# CH32V005F6U.net
KiCad netlist of a schematic drawn in Altium Designer
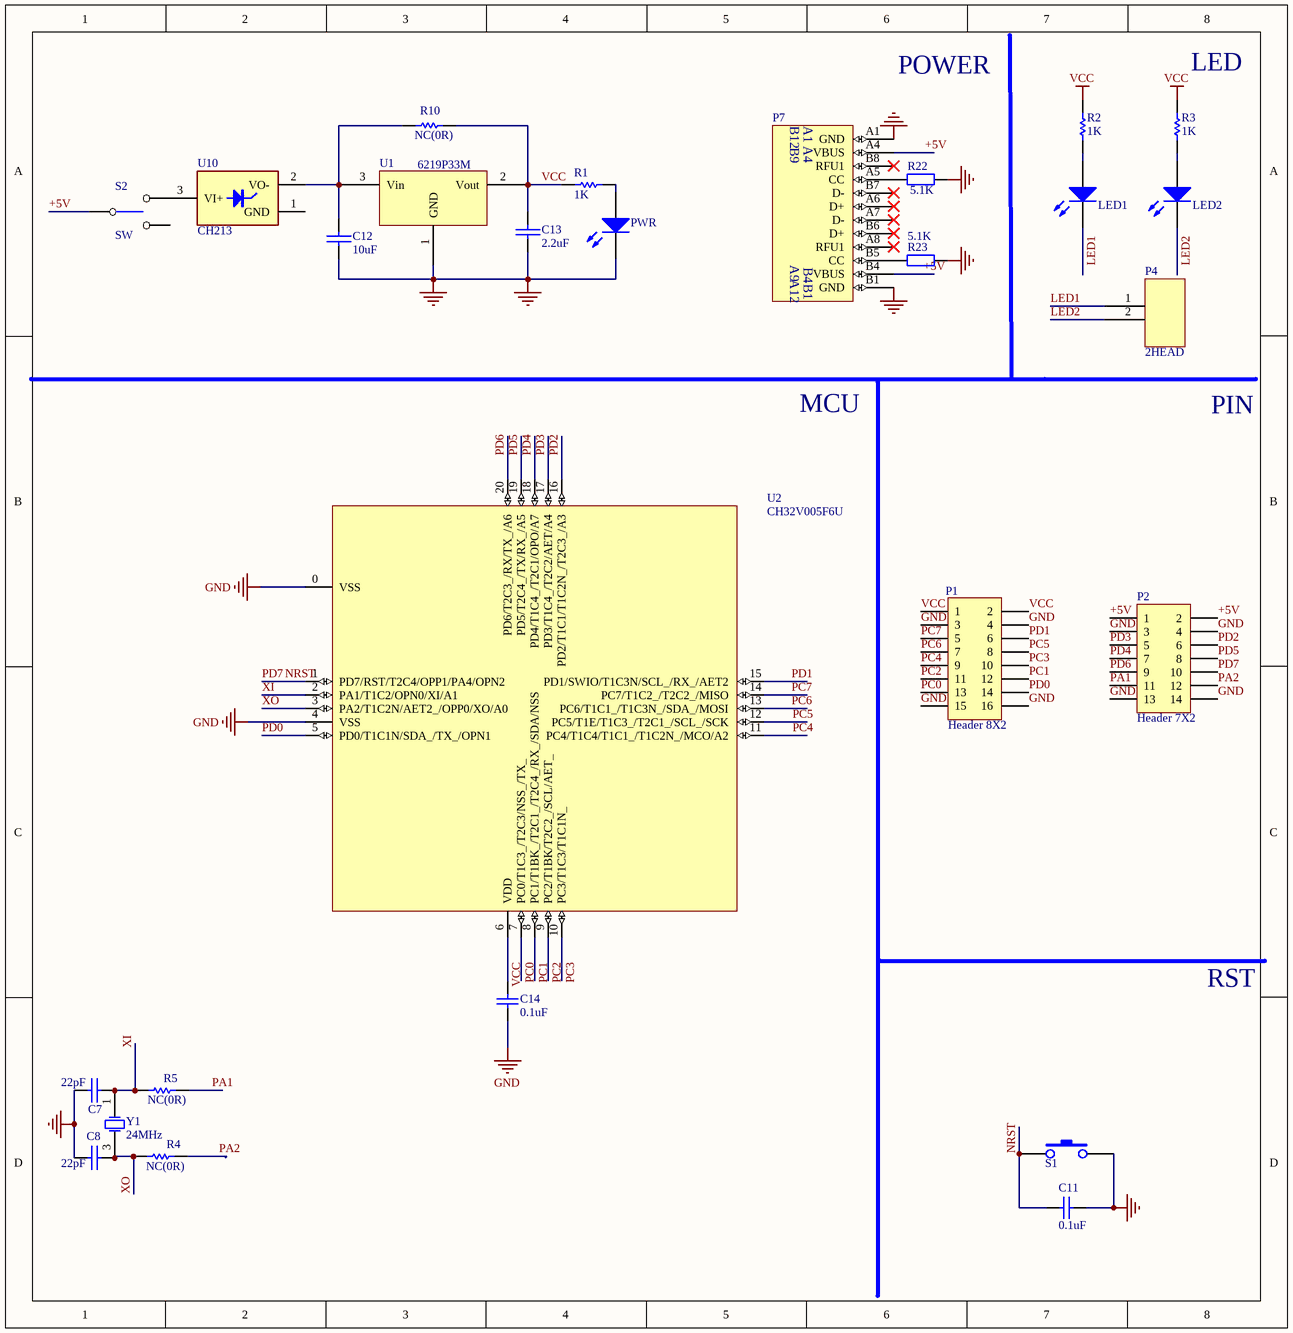
[diagram p0: CH32V005F6U.SchDoc]

(export (version "E")
  (design (tool "Eeschema 10.0.6"))
  (components
    (comp (ref "C7")
      (value "22pF")
      (footprint "0402_C")
      (description "Capacitor")
      (libsource (lib "*") (part "CAP"))
    )
    (comp (ref "C8")
      (value "22pF")
      (footprint "0402_C")
      (description "Capacitor")
      (libsource (lib "*") (part "CAP"))
    )
    (comp (ref "C11")
      (value "0.1uF")
      (footprint "0603_C")
      (description "Capacitor")
      (fields (field (name "PUBLISHER") "Altium Limited"))
      (libsource (lib "*") (part "Cap"))
    )
    (comp (ref "C12")
      (value "10uF")
      (footprint "0603_C")
      (description "Capacitor")
      (libsource (lib "wch_sch_others") (part "CAP"))
    )
    (comp (ref "C13")
      (value "2.2uF")
      (footprint "0402_C")
      (description "Capacitor")
      (libsource (lib "wch_sch_others") (part "CAP"))
    )
    (comp (ref "C14")
      (value "0.1uF")
      (footprint "0603_C")
      (description "Capacitor")
      (fields (field (name "PUBLISHER") "Altium Limited"))
      (libsource (lib "*") (part "Cap"))
    )
    (comp (ref "LED1")
      (value "LED1   blue")
      (footprint "0603+")
      (description "Typical INFRARED GaAs LED")
      (fields (field (name "PUBLISHER") "Altium Limited"))
      (libsource (lib "*") (part "LED0"))
    )
    (comp (ref "LED2")
      (value "LED2  blue")
      (footprint "0603+")
      (description "Typical INFRARED GaAs LED")
      (fields (field (name "PUBLISHER") "Altium Limited"))
      (libsource (lib "*") (part "LED0"))
    )
    (comp (ref "P1")
      (value "Header 8X2")
      (footprint "HDR2X8")
      (description "Header, 8-Pin, Dual row")
      (fields (field (name "PUBLISHER") "Altium Limited"))
      (libsource (lib "Miscellaneous Connectors") (part "Header 8X2"))
    )
    (comp (ref "P2")
      (value "Header 7X2")
      (footprint "HDR2X7")
      (description "Header, 7-Pin, Dual row")
      (fields (field (name "PUBLISHER") "Altium Limited"))
      (libsource (lib "Miscellaneous Connectors") (part "Header 7X2"))
    )
    (comp (ref "P4") (value "2HEAD") (footprint "SIP2-2.54mm") (libsource (lib "*") (part "2HEAD")))
    (comp (ref "P7")
      (value "TYPE-C")
      (footprint "TYPE-C-Receptacle-2.0")
      (libsource (lib "*") (part "TYPE-C1"))
    )
    (comp (ref "PWR")
      (value "POWER  red")
      (footprint "0603+")
      (description "Typical INFRARED GaAs LED")
      (fields (field (name "PUBLISHER") "Altium Limited"))
      (libsource (lib "") (part "LED0_1"))
    )
    (comp (ref "R1")
      (value "1K")
      (footprint "0402")
      (description "Semiconductor Resistor")
      (fields (field (name "PUBLISHER") "Altium Limited"))
      (libsource (lib "*") (part "Res Semi"))
    )
    (comp (ref "R2")
      (value "1K")
      (footprint "0402")
      (description "Semiconductor Resistor")
      (fields (field (name "PUBLISHER") "Altium Limited"))
      (libsource (lib "*") (part "Res Semi"))
    )
    (comp (ref "R3")
      (value "1K")
      (footprint "0402")
      (description "Semiconductor Resistor")
      (fields (field (name "PUBLISHER") "Altium Limited"))
      (libsource (lib "*") (part "Res Semi"))
    )
    (comp (ref "R4")
      (value "NC(0R)")
      (footprint "0402")
      (description "Semiconductor Resistor")
      (fields (field (name "Comment") "0R") (field (name "PUBLISHER") "Altium Limited"))
      (libsource (lib "*") (part "Res Semi"))
    )
    (comp (ref "R5")
      (value "NC(0R)")
      (footprint "0402")
      (description "Semiconductor Resistor")
      (fields (field (name "Comment") "0R") (field (name "PUBLISHER") "Altium Limited"))
      (libsource (lib "*") (part "Res Semi"))
    )
    (comp (ref "R10")
      (value "NC(0R)")
      (footprint "0402")
      (description "Semiconductor Resistor")
      (fields (field (name "Comment") "0R") (field (name "PUBLISHER") "Altium Limited"))
      (libsource (lib "*") (part "Res Semi"))
    )
    (comp (ref "R22")
      (value "5.1K")
      (footprint "0402")
      (description "Resistor")
      (libsource (lib "Miscellaneous Devices") (part "Res2"))
    )
    (comp (ref "R23")
      (value "5.1K")
      (footprint "0402")
      (description "Resistor")
      (libsource (lib "Miscellaneous Devices") (part "Res2"))
    )
    (comp (ref "S1") (value "NRST") (footprint "SMD_6.1x3.65x2.5mm-KEY") (libsource (lib "*") (part "KEY")))
    (comp (ref "S2") (value "SW") (footprint "SW1") (libsource (lib "*") (part "SW")))
    (comp (ref "U1")
      (value "6219P33M")
      (footprint "SOT-23")
      (libsource (lib "wch_sch_others") (part "6219P33M"))
    )
    (comp (ref "U2")
      (value "CH32V005F6U")
      (footprint "QFN20_3X3")
      (description "RISC-V MCU, 48MHz, ADC/OPA/2*UART/I2C/SPI")
      (libsource (lib "DHXXXSCH") (part "CH32V005F6U6"))
    )
    (comp (ref "U10")
      (value "CH213")
      (footprint "SOT-23-3")
      (description "Ideal Diode 5V*1A")
      (libsource (lib "CHXXX") (part "CH213E"))
    )
    (comp (ref "Y1")
      (value "24MHz")
      (footprint "XT3225")
      (description "Crystal Oscillator")
      (fields (field (name "PUBLISHER") "Altium Limited"))
      (libsource (lib "*") (part "XTAL"))
    )
  )
  (nets
    (net (code "1") (name "/+5V") (class "Default")
      (node (ref "P2") (pin "1") (pinfunction "1_1") (pintype "passive"))
      (node (ref "P2") (pin "2") (pinfunction "2_2") (pintype "passive"))
      (node (ref "P7") (pin "A4") (pinfunction "VBUS_A4") (pintype "bidirectional"))
      (node (ref "P7") (pin "B4") (pinfunction "VBUS_B4") (pintype "bidirectional"))
      (node (ref "S2") (pin "1") (pinfunction "1_1") (pintype "passive"))
    )
    (net (code "2") (name "/LED1") (class "Default")
      (node (ref "LED1") (pin "2") (pinfunction "K_2") (pintype "passive"))
      (node (ref "P4") (pin "1") (pintype "passive"))
    )
    (net (code "3") (name "/LED2") (class "Default")
      (node (ref "LED2") (pin "2") (pinfunction "K_2") (pintype "passive"))
      (node (ref "P4") (pin "2") (pintype "passive"))
    )
    (net (code "4") (name "/NRST") (class "Default")
      (node (ref "C11") (pin "2") (pinfunction "2_2") (pintype "passive"))
      (node (ref "P2") (pin "10") (pinfunction "10_10") (pintype "passive"))
      (node (ref "S1") (pin "1") (pinfunction "1_1") (pintype "passive"))
      (node (ref "U2") (pin "1") (pinfunction "PD7/RST/T2C4/OPP1/PA4/OPN2_1") (pintype "bidirectional"))
    )
    (net (code "5") (name "/PA1") (class "Default")
      (node (ref "P2") (pin "11") (pinfunction "11_11") (pintype "passive"))
      (node (ref "R5") (pin "2") (pinfunction "2_2") (pintype "passive"))
    )
    (net (code "6") (name "/PA2") (class "Default")
      (node (ref "P2") (pin "12") (pinfunction "12_12") (pintype "passive"))
      (node (ref "R4") (pin "2") (pinfunction "2_2") (pintype "passive"))
    )
    (net (code "7") (name "/PC0") (class "Default")
      (node (ref "P1") (pin "13") (pinfunction "13_13") (pintype "passive"))
      (node (ref "U2") (pin "7") (pinfunction "PC0/T1C3_/T2C3/NSS_/TX__7") (pintype "bidirectional"))
    )
    (net (code "8") (name "/PC1") (class "Default")
      (node (ref "P1") (pin "12") (pinfunction "12_12") (pintype "passive"))
      (node (ref "U2") (pin "8") (pinfunction "PC1/T1BK_/T2C1_/T2C4_/RX_/SDA/NSS_8") (pintype "bidirectional"))
    )
    (net (code "9") (name "/PC2") (class "Default")
      (node (ref "P1") (pin "11") (pinfunction "11_11") (pintype "passive"))
      (node (ref "U2") (pin "9") (pinfunction "PC2/T1BK/T2C2_/SCL/AET__9") (pintype "bidirectional"))
    )
    (net (code "10") (name "/PC3") (class "Default")
      (node (ref "P1") (pin "10") (pinfunction "10_10") (pintype "passive"))
      (node (ref "U2") (pin "10") (pinfunction "PC3/T1C3/T1C1N__10") (pintype "bidirectional"))
    )
    (net (code "11") (name "/PC4") (class "Default")
      (node (ref "P1") (pin "9") (pinfunction "9_9") (pintype "passive"))
      (node (ref "U2") (pin "11") (pinfunction "PC4/T1C4/T1C1_/T1C2N_/MCO/A2_11") (pintype "bidirectional"))
    )
    (net (code "12") (name "/PC5") (class "Default")
      (node (ref "P1") (pin "8") (pinfunction "8_8") (pintype "passive"))
      (node (ref "U2") (pin "12") (pinfunction "PC5/T1E/T1C3_/T2C1_/SCL_/SCK_12") (pintype "bidirectional"))
    )
    (net (code "13") (name "/PC6") (class "Default")
      (node (ref "P1") (pin "7") (pinfunction "7_7") (pintype "passive"))
      (node (ref "U2") (pin "13") (pinfunction "PC6/T1C1_/T1C3N_/SDA_/MOSI_13") (pintype "bidirectional"))
    )
    (net (code "14") (name "/PC7") (class "Default")
      (node (ref "P1") (pin "5") (pinfunction "5_5") (pintype "passive"))
      (node (ref "U2") (pin "14") (pinfunction "PC7/T1C2_/T2C2_/MISO_14") (pintype "bidirectional"))
    )
    (net (code "15") (name "/PD0") (class "Default")
      (node (ref "P1") (pin "14") (pinfunction "14_14") (pintype "passive"))
      (node (ref "U2") (pin "5") (pinfunction "PD0/T1C1N/SDA_/TX_/OPN1_5") (pintype "bidirectional"))
    )
    (net (code "16") (name "/PD1") (class "Default")
      (node (ref "P1") (pin "6") (pinfunction "6_6") (pintype "passive"))
      (node (ref "U2") (pin "15") (pinfunction "PD1/SWIO/T1C3N/SCL_/RX_/AET2_15") (pintype "bidirectional"))
    )
    (net (code "17") (name "/PD2") (class "Default")
      (node (ref "P2") (pin "6") (pinfunction "6_6") (pintype "passive"))
      (node (ref "U2") (pin "16") (pinfunction "PD2/T1C1/T1C2N_/T2C3_/A3_16") (pintype "bidirectional"))
    )
    (net (code "18") (name "/PD3") (class "Default")
      (node (ref "P2") (pin "5") (pinfunction "5_5") (pintype "passive"))
      (node (ref "U2") (pin "17") (pinfunction "PD3/T1C4_/T2C2/AET/A4_17") (pintype "bidirectional"))
    )
    (net (code "19") (name "/PD4") (class "Default")
      (node (ref "P2") (pin "7") (pinfunction "7_7") (pintype "passive"))
      (node (ref "U2") (pin "18") (pinfunction "PD4/T1C4_/T2C1/OPO/A7_18") (pintype "bidirectional"))
    )
    (net (code "20") (name "/PD5") (class "Default")
      (node (ref "P2") (pin "8") (pinfunction "8_8") (pintype "passive"))
      (node (ref "U2") (pin "19") (pinfunction "PD5/T2C4_/TX/RX_/A5_19") (pintype "bidirectional"))
    )
    (net (code "21") (name "/PD6") (class "Default")
      (node (ref "P2") (pin "9") (pinfunction "9_9") (pintype "passive"))
      (node (ref "U2") (pin "20") (pinfunction "PD6/T2C3_/RX/TX_/A6_20") (pintype "bidirectional"))
    )
    (net (code "22") (name "/XI") (class "Default")
      (node (ref "C7") (pin "2") (pinfunction "2_2") (pintype "passive"))
      (node (ref "R5") (pin "1") (pinfunction "1_1") (pintype "passive"))
      (node (ref "U2") (pin "2") (pinfunction "PA1/T1C2/OPN0/XI/A1_2") (pintype "bidirectional"))
      (node (ref "Y1") (pin "1") (pinfunction "OSC1_1") (pintype "passive"))
    )
    (net (code "23") (name "/XO") (class "Default")
      (node (ref "C8") (pin "2") (pinfunction "2_2") (pintype "passive"))
      (node (ref "R4") (pin "1") (pinfunction "1_1") (pintype "passive"))
      (node (ref "U2") (pin "3") (pinfunction "PA2/T1C2N/AET2_/OPP0/XO/A0_3") (pintype "bidirectional"))
      (node (ref "Y1") (pin "3") (pinfunction "OSC2_3") (pintype "passive"))
    )
    (net (code "24") (name "GND") (class "Default")
      (node (ref "C11") (pin "1") (pinfunction "1_1") (pintype "passive"))
      (node (ref "C12") (pin "2") (pinfunction "2_2") (pintype "passive"))
      (node (ref "C13") (pin "1") (pinfunction "1_1") (pintype "passive"))
      (node (ref "C14") (pin "2") (pinfunction "2_2") (pintype "passive"))
      (node (ref "C7") (pin "1") (pinfunction "1_1") (pintype "passive"))
      (node (ref "C8") (pin "1") (pinfunction "1_1") (pintype "passive"))
      (node (ref "P1") (pin "15") (pinfunction "15_15") (pintype "passive"))
      (node (ref "P1") (pin "16") (pinfunction "16_16") (pintype "passive"))
      (node (ref "P1") (pin "3") (pinfunction "3_3") (pintype "passive"))
      (node (ref "P1") (pin "4") (pinfunction "4_4") (pintype "passive"))
      (node (ref "P2") (pin "13") (pinfunction "13_13") (pintype "passive"))
      (node (ref "P2") (pin "14") (pinfunction "14_14") (pintype "passive"))
      (node (ref "P2") (pin "3") (pinfunction "3_3") (pintype "passive"))
      (node (ref "P2") (pin "4") (pinfunction "4_4") (pintype "passive"))
      (node (ref "P7") (pin "A1") (pinfunction "GND_A1") (pintype "bidirectional"))
      (node (ref "P7") (pin "B1") (pinfunction "GND_B1") (pintype "bidirectional"))
      (node (ref "PWR") (pin "2") (pinfunction "K_2") (pintype "passive"))
      (node (ref "R22") (pin "2") (pinfunction "2_2") (pintype "passive"))
      (node (ref "R23") (pin "2") (pinfunction "2_2") (pintype "passive"))
      (node (ref "S1") (pin "2") (pinfunction "2_2") (pintype "passive"))
      (node (ref "U1") (pin "1") (pinfunction "GND_1") (pintype "passive"))
      (node (ref "U2") (pin "0") (pinfunction "VSS_0") (pintype "power_in"))
      (node (ref "U2") (pin "4") (pinfunction "VSS_4") (pintype "power_in"))
    )
    (net (code "25") (name "Net-(LED1-A)") (class "Default")
      (node (ref "LED1") (pin "1") (pinfunction "A_1") (pintype "passive"))
      (node (ref "R2") (pin "2") (pinfunction "2_2") (pintype "passive"))
    )
    (net (code "26") (name "Net-(LED2-A)") (class "Default")
      (node (ref "LED2") (pin "1") (pinfunction "A_1") (pintype "passive"))
      (node (ref "R3") (pin "2") (pinfunction "2_2") (pintype "passive"))
    )
    (net (code "27") (name "Net-(P7-CC-PadA5)") (class "Default")
      (node (ref "P7") (pin "A5") (pinfunction "CC_A5") (pintype "bidirectional"))
      (node (ref "R22") (pin "1") (pinfunction "1_1") (pintype "passive"))
    )
    (net (code "28") (name "Net-(P7-CC-PadB5)") (class "Default")
      (node (ref "P7") (pin "B5") (pinfunction "CC_B5") (pintype "bidirectional"))
      (node (ref "R23") (pin "1") (pinfunction "1_1") (pintype "passive"))
    )
    (net (code "29") (name "Net-(PWR-A)") (class "Default")
      (node (ref "PWR") (pin "1") (pinfunction "A_1") (pintype "passive"))
      (node (ref "R1") (pin "1") (pinfunction "1_1") (pintype "passive"))
    )
    (net (code "30") (name "Net-(U1-Vin)") (class "Default")
      (node (ref "C12") (pin "1") (pinfunction "1_1") (pintype "passive"))
      (node (ref "R10") (pin "1") (pinfunction "1_1") (pintype "passive"))
      (node (ref "U1") (pin "3") (pinfunction "Vin_3") (pintype "passive"))
      (node (ref "U10") (pin "2") (pinfunction "VO-_2") (pintype "power_in"))
    )
    (net (code "31") (name "Net-(U10-VI+)") (class "Default")
      (node (ref "S2") (pin "3") (pinfunction "3_3") (pintype "passive"))
      (node (ref "U10") (pin "3") (pinfunction "VI+_3") (pintype "power_in"))
    )
    (net (code "32") (name "VCC") (class "Default")
      (node (ref "C13") (pin "2") (pinfunction "2_2") (pintype "passive"))
      (node (ref "C14") (pin "1") (pinfunction "1_1") (pintype "passive"))
      (node (ref "P1") (pin "1") (pinfunction "1_1") (pintype "passive"))
      (node (ref "P1") (pin "2") (pinfunction "2_2") (pintype "passive"))
      (node (ref "R1") (pin "2") (pinfunction "2_2") (pintype "passive"))
      (node (ref "R10") (pin "2") (pinfunction "2_2") (pintype "passive"))
      (node (ref "R2") (pin "1") (pinfunction "1_1") (pintype "passive"))
      (node (ref "R3") (pin "1") (pinfunction "1_1") (pintype "passive"))
      (node (ref "U1") (pin "2") (pinfunction "Vout_2") (pintype "passive"))
      (node (ref "U2") (pin "6") (pinfunction "VDD_6") (pintype "power_in"))
    )
    (net (code "33") (name "unconnected-(P7-D+-PadA6)") (class "Default")
      (node (ref "P7") (pin "A6") (pinfunction "D+_A6") (pintype "bidirectional+no_connect"))
    )
    (net (code "34") (name "unconnected-(P7-D+-PadB6)") (class "Default")
      (node (ref "P7") (pin "B6") (pinfunction "D+_B6") (pintype "bidirectional+no_connect"))
    )
    (net (code "35") (name "unconnected-(P7-D--PadA7)") (class "Default")
      (node (ref "P7") (pin "A7") (pinfunction "D-_A7") (pintype "bidirectional+no_connect"))
    )
    (net (code "36") (name "unconnected-(P7-D--PadB7)") (class "Default")
      (node (ref "P7") (pin "B7") (pinfunction "D-_B7") (pintype "bidirectional+no_connect"))
    )
    (net (code "37") (name "unconnected-(P7-RFU1-PadA8)") (class "Default")
      (node (ref "P7") (pin "A8") (pinfunction "RFU1_A8") (pintype "bidirectional+no_connect"))
    )
    (net (code "38") (name "unconnected-(P7-RFU1-PadB8)") (class "Default")
      (node (ref "P7") (pin "B8") (pinfunction "RFU1_B8") (pintype "bidirectional+no_connect"))
    )
    (net (code "39") (name "unconnected-(S2-Pad2)") (class "Default")
      (node (ref "S2") (pin "2") (pinfunction "2_2") (pintype "passive"))
    )
    (net (code "40") (name "unconnected-(U10-GND-Pad1)") (class "Default")
      (node (ref "U10") (pin "1") (pinfunction "GND_1") (pintype "power_in"))
    )
  )
)
